# nf10_addon.net
KiCad netlist of a schematic drawn in Altium Designer
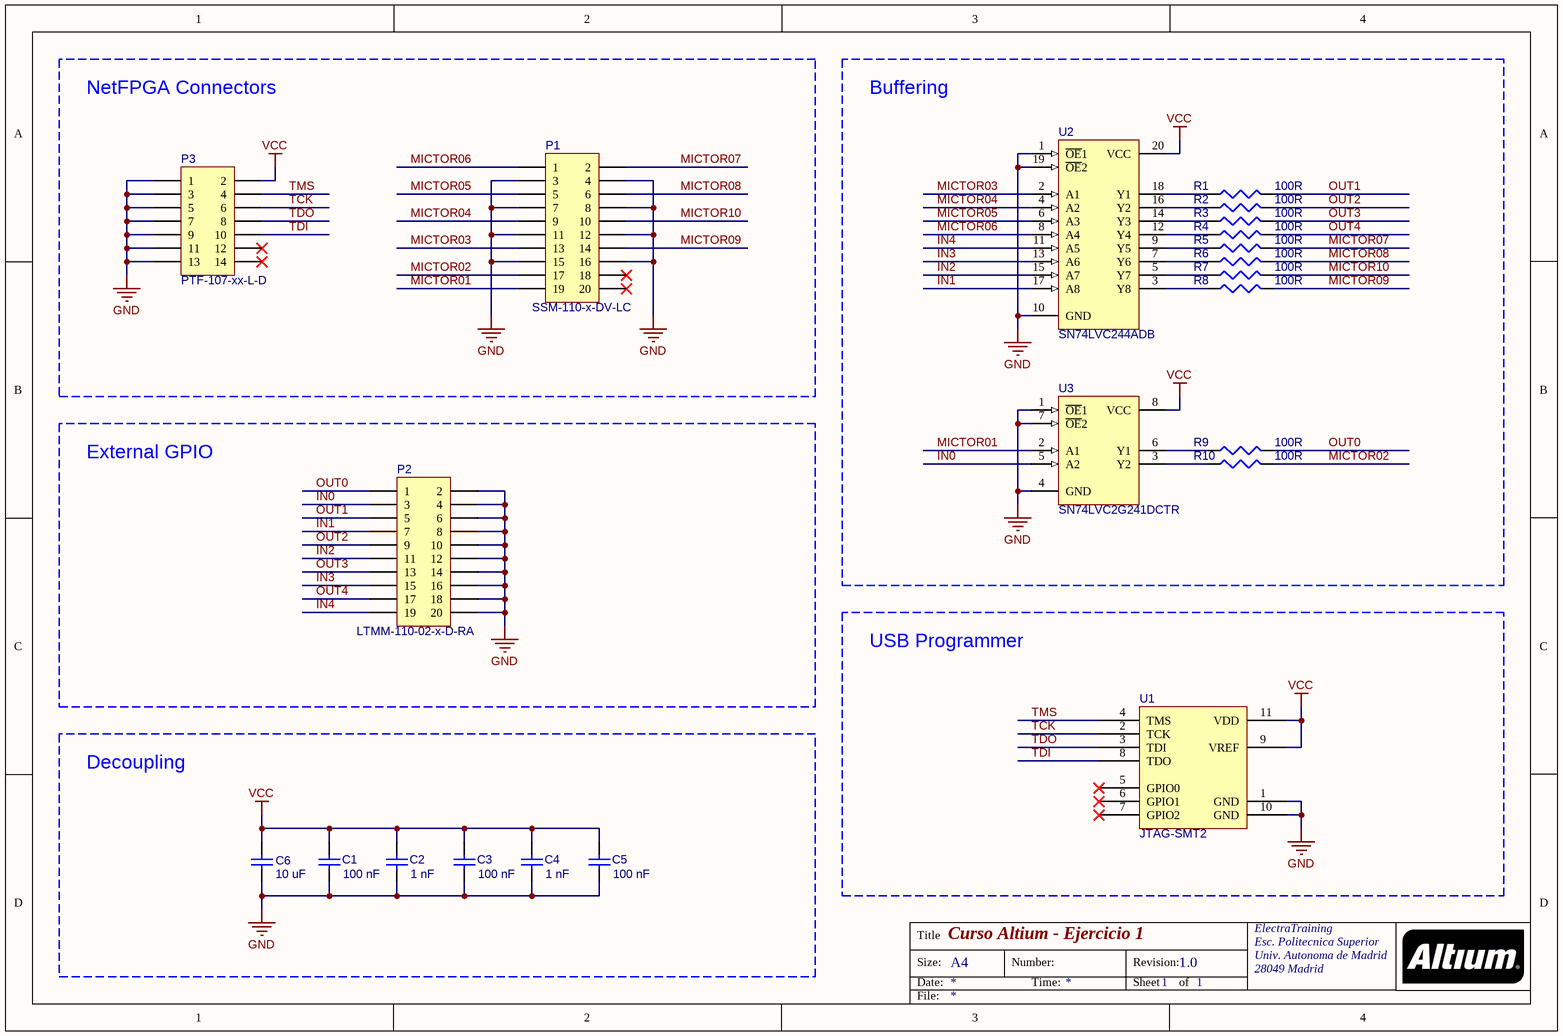
[diagram p0: nf10_addon.SchDoc]

(export (version "E")
  (design (tool "Eeschema 10.0.6"))
  (components
    (comp (ref "C1")
      (value "100 nF")
      (footprint "CAPC0603(1608)100_N")
      (description "Capacitor")
      (fields (field (name "Comment") "Cap") (field (name "PUBLISHER") "Altium Limited"))
      (libsource (lib "Miscellaneous Devices") (part "Cap"))
    )
    (comp (ref "C2")
      (value "1 nF")
      (footprint "CAPC0603(1608)100_N")
      (description "Capacitor")
      (fields (field (name "Comment") "Cap") (field (name "PUBLISHER") "Altium Limited"))
      (libsource (lib "Miscellaneous Devices") (part "Cap"))
    )
    (comp (ref "C3")
      (value "100 nF")
      (footprint "CAPC0603(1608)100_N")
      (description "Capacitor")
      (fields (field (name "Comment") "Cap") (field (name "PUBLISHER") "Altium Limited"))
      (libsource (lib "Miscellaneous Devices") (part "Cap"))
    )
    (comp (ref "C4")
      (value "1 nF")
      (footprint "CAPC0603(1608)100_N")
      (description "Capacitor")
      (fields (field (name "Comment") "Cap") (field (name "PUBLISHER") "Altium Limited"))
      (libsource (lib "Miscellaneous Devices") (part "Cap"))
    )
    (comp (ref "C5")
      (value "100 nF")
      (footprint "CAPC0603(1608)100_N")
      (description "Capacitor")
      (fields (field (name "Comment") "Cap") (field (name "PUBLISHER") "Altium Limited"))
      (libsource (lib "Miscellaneous Devices") (part "Cap"))
    )
    (comp (ref "C6")
      (value "10 uF")
      (footprint "CAPC1206(3216)100_N")
      (description "Capacitor")
      (fields (field (name "Comment") "Cap") (field (name "PUBLISHER") "Altium Limited"))
      (libsource (lib "Miscellaneous Devices") (part "Cap"))
    )
    (comp (ref "P1")
      (value "SSM-110-x-DV-LC")
      (footprint "SSM-110-X-DV-LC")
      (description "Samtec SSM-110-x-DV-LC")
      (fields (field (name "PUBLISHER") "Altium Limited"))
      (libsource (lib "nf10_addon") (part "SSM-110-x-DV-LC"))
    )
    (comp (ref "P2")
      (value "LTMM-110-02-x-D-RA")
      (footprint "LTMM-110-02-X-D-RA")
      (description "Samtec LTMM-110-02-x-D-RA")
      (fields (field (name "PUBLISHER") "Altium Limited"))
      (libsource (lib "nf10_addon") (part "LTMM-110-02-x-D-RA"))
    )
    (comp (ref "P3")
      (value "PTF-107-xx-L-D")
      (footprint "PTF-107-XX-L-D")
      (description "Samtec PTF-107-xx-L-D")
      (fields (field (name "PUBLISHER") "Altium Limited"))
      (libsource (lib "nf10_addon") (part "PTF-107-xx-L-D"))
    )
    (comp (ref "R1")
      (value "100R")
      (footprint "RESC0603(1608)_N")
      (description "Resistor")
      (fields (field (name "Comment") "Res3") (field (name "PUBLISHER") "Altium Limited"))
      (libsource (lib "Miscellaneous Devices") (part "Res3"))
    )
    (comp (ref "R2")
      (value "100R")
      (footprint "RESC0603(1608)_N")
      (description "Resistor")
      (fields (field (name "Comment") "Res3") (field (name "PUBLISHER") "Altium Limited"))
      (libsource (lib "Miscellaneous Devices") (part "Res3"))
    )
    (comp (ref "R3")
      (value "100R")
      (footprint "RESC0603(1608)_N")
      (description "Resistor")
      (fields (field (name "Comment") "Res3") (field (name "PUBLISHER") "Altium Limited"))
      (libsource (lib "Miscellaneous Devices") (part "Res3"))
    )
    (comp (ref "R4")
      (value "100R")
      (footprint "RESC0603(1608)_N")
      (description "Resistor")
      (fields (field (name "Comment") "Res3") (field (name "PUBLISHER") "Altium Limited"))
      (libsource (lib "Miscellaneous Devices") (part "Res3"))
    )
    (comp (ref "R5")
      (value "100R")
      (footprint "RESC0603(1608)_N")
      (description "Resistor")
      (fields (field (name "Comment") "Res3") (field (name "PUBLISHER") "Altium Limited"))
      (libsource (lib "Miscellaneous Devices") (part "Res3"))
    )
    (comp (ref "R6")
      (value "100R")
      (footprint "RESC0603(1608)_N")
      (description "Resistor")
      (fields (field (name "Comment") "Res3") (field (name "PUBLISHER") "Altium Limited"))
      (libsource (lib "Miscellaneous Devices") (part "Res3"))
    )
    (comp (ref "R7")
      (value "100R")
      (footprint "RESC0603(1608)_N")
      (description "Resistor")
      (fields (field (name "Comment") "Res3") (field (name "PUBLISHER") "Altium Limited"))
      (libsource (lib "Miscellaneous Devices") (part "Res3"))
    )
    (comp (ref "R8")
      (value "100R")
      (footprint "RESC0603(1608)_N")
      (description "Resistor")
      (fields (field (name "Comment") "Res3") (field (name "PUBLISHER") "Altium Limited"))
      (libsource (lib "Miscellaneous Devices") (part "Res3"))
    )
    (comp (ref "R9")
      (value "100R")
      (footprint "RESC0603(1608)_N")
      (description "Resistor")
      (fields (field (name "Comment") "Res3") (field (name "PUBLISHER") "Altium Limited"))
      (libsource (lib "Miscellaneous Devices") (part "Res3"))
    )
    (comp (ref "R10")
      (value "100R")
      (footprint "RESC0603(1608)_N")
      (description "Resistor")
      (fields (field (name "Comment") "Res3") (field (name "PUBLISHER") "Altium Limited"))
      (libsource (lib "Miscellaneous Devices") (part "Res3"))
    )
    (comp (ref "U1")
      (value "JTAG-SMT2")
      (footprint "JTAG-SMT2")
      (libsource (lib "NetFPGA10G_Addon") (part "JTAG_SMT2"))
    )
    (comp (ref "U2")
      (value "SN74LVC244ADB")
      (footprint "DB020_N")
      (description "Octal Buffer/Driver with 3-State Outputs")
      (fields (field (name "PUBLISHER") "Altium Limited"))
      (libsource (lib "TI Logic Buffer Line Driver") (part "SN74LVC244ADB"))
    )
    (comp (ref "U3")
      (value "SN74LVC2G241DCTR")
      (footprint "DCT08_N")
      (description "Quadruple Bus Buffer Gate with 3- State Outputs")
      (fields (field (name "PUBLISHER") "Altium Limited"))
      (libsource (lib "nf10_addon") (part "SN74LVC2G241DCTR"))
    )
  )
  (nets
    (net (code "1") (name "/IN0") (class "Default")
      (node (ref "P2") (pin "3") (pinfunction "3_3") (pintype "passive"))
      (node (ref "U3") (pin "5") (pinfunction "A2_5") (pintype "input"))
    )
    (net (code "2") (name "/IN1") (class "Default")
      (node (ref "P2") (pin "7") (pinfunction "7_7") (pintype "passive"))
      (node (ref "U2") (pin "17") (pinfunction "A8_17") (pintype "input"))
    )
    (net (code "3") (name "/IN2") (class "Default")
      (node (ref "P2") (pin "11") (pinfunction "11_11") (pintype "passive"))
      (node (ref "U2") (pin "15") (pinfunction "A7_15") (pintype "input"))
    )
    (net (code "4") (name "/IN3") (class "Default")
      (node (ref "P2") (pin "15") (pinfunction "15_15") (pintype "passive"))
      (node (ref "U2") (pin "13") (pinfunction "A6_13") (pintype "input"))
    )
    (net (code "5") (name "/IN4") (class "Default")
      (node (ref "P2") (pin "19") (pinfunction "19_19") (pintype "passive"))
      (node (ref "U2") (pin "11") (pinfunction "A5_11") (pintype "input"))
    )
    (net (code "6") (name "/MICTOR01") (class "Default")
      (node (ref "P1") (pin "19") (pinfunction "19_19") (pintype "passive"))
      (node (ref "U3") (pin "2") (pinfunction "A1_2") (pintype "input"))
    )
    (net (code "7") (name "/MICTOR02") (class "Default")
      (node (ref "P1") (pin "17") (pinfunction "17_17") (pintype "passive"))
      (node (ref "R10") (pin "2") (pinfunction "2_2") (pintype "passive"))
    )
    (net (code "8") (name "/MICTOR03") (class "Default")
      (node (ref "P1") (pin "13") (pinfunction "13_13") (pintype "passive"))
      (node (ref "U2") (pin "2") (pinfunction "A1_2") (pintype "input"))
    )
    (net (code "9") (name "/MICTOR04") (class "Default")
      (node (ref "P1") (pin "9") (pinfunction "9_9") (pintype "passive"))
      (node (ref "U2") (pin "4") (pinfunction "A2_4") (pintype "input"))
    )
    (net (code "10") (name "/MICTOR05") (class "Default")
      (node (ref "P1") (pin "5") (pinfunction "5_5") (pintype "passive"))
      (node (ref "U2") (pin "6") (pinfunction "A3_6") (pintype "input"))
    )
    (net (code "11") (name "/MICTOR06") (class "Default")
      (node (ref "P1") (pin "1") (pinfunction "1_1") (pintype "passive"))
      (node (ref "U2") (pin "8") (pinfunction "A4_8") (pintype "input"))
    )
    (net (code "12") (name "/MICTOR07") (class "Default")
      (node (ref "P1") (pin "2") (pinfunction "2_2") (pintype "passive"))
      (node (ref "R5") (pin "2") (pinfunction "2_2") (pintype "passive"))
    )
    (net (code "13") (name "/MICTOR08") (class "Default")
      (node (ref "P1") (pin "6") (pinfunction "6_6") (pintype "passive"))
      (node (ref "R6") (pin "2") (pinfunction "2_2") (pintype "passive"))
    )
    (net (code "14") (name "/MICTOR09") (class "Default")
      (node (ref "P1") (pin "14") (pinfunction "14_14") (pintype "passive"))
      (node (ref "R8") (pin "2") (pinfunction "2_2") (pintype "passive"))
    )
    (net (code "15") (name "/MICTOR10") (class "Default")
      (node (ref "P1") (pin "10") (pinfunction "10_10") (pintype "passive"))
      (node (ref "R7") (pin "2") (pinfunction "2_2") (pintype "passive"))
    )
    (net (code "16") (name "/OUT0") (class "Default")
      (node (ref "P2") (pin "1") (pinfunction "1_1") (pintype "passive"))
      (node (ref "R9") (pin "2") (pinfunction "2_2") (pintype "passive"))
    )
    (net (code "17") (name "/OUT1") (class "Default")
      (node (ref "P2") (pin "5") (pinfunction "5_5") (pintype "passive"))
      (node (ref "R1") (pin "2") (pinfunction "2_2") (pintype "passive"))
    )
    (net (code "18") (name "/OUT2") (class "Default")
      (node (ref "P2") (pin "9") (pinfunction "9_9") (pintype "passive"))
      (node (ref "R2") (pin "2") (pinfunction "2_2") (pintype "passive"))
    )
    (net (code "19") (name "/OUT3") (class "Default")
      (node (ref "P2") (pin "13") (pinfunction "13_13") (pintype "passive"))
      (node (ref "R3") (pin "2") (pinfunction "2_2") (pintype "passive"))
    )
    (net (code "20") (name "/OUT4") (class "Default")
      (node (ref "P2") (pin "17") (pinfunction "17_17") (pintype "passive"))
      (node (ref "R4") (pin "2") (pinfunction "2_2") (pintype "passive"))
    )
    (net (code "21") (name "/TCK") (class "Default")
      (node (ref "P3") (pin "6") (pinfunction "6_6") (pintype "passive"))
      (node (ref "U1") (pin "2") (pinfunction "TCK_2") (pintype "passive"))
    )
    (net (code "22") (name "/TDI") (class "Default")
      (node (ref "P3") (pin "10") (pinfunction "10_10") (pintype "passive"))
      (node (ref "U1") (pin "8") (pinfunction "TDO_8") (pintype "passive"))
    )
    (net (code "23") (name "/TDO") (class "Default")
      (node (ref "P3") (pin "8") (pinfunction "8_8") (pintype "passive"))
      (node (ref "U1") (pin "3") (pinfunction "TDI_3") (pintype "passive"))
    )
    (net (code "24") (name "/TMS") (class "Default")
      (node (ref "P3") (pin "4") (pinfunction "4_4") (pintype "passive"))
      (node (ref "U1") (pin "4") (pinfunction "TMS_4") (pintype "passive"))
    )
    (net (code "25") (name "GND") (class "Default")
      (node (ref "C1") (pin "1") (pinfunction "1_1") (pintype "passive"))
      (node (ref "C2") (pin "1") (pinfunction "1_1") (pintype "passive"))
      (node (ref "C3") (pin "1") (pinfunction "1_1") (pintype "passive"))
      (node (ref "C4") (pin "1") (pinfunction "1_1") (pintype "passive"))
      (node (ref "C5") (pin "1") (pinfunction "1_1") (pintype "passive"))
      (node (ref "C6") (pin "1") (pinfunction "1_1") (pintype "passive"))
      (node (ref "P1") (pin "11") (pinfunction "11_11") (pintype "passive"))
      (node (ref "P1") (pin "12") (pinfunction "12_12") (pintype "passive"))
      (node (ref "P1") (pin "15") (pinfunction "15_15") (pintype "passive"))
      (node (ref "P1") (pin "16") (pinfunction "16_16") (pintype "passive"))
      (node (ref "P1") (pin "3") (pinfunction "3_3") (pintype "passive"))
      (node (ref "P1") (pin "4") (pinfunction "4_4") (pintype "passive"))
      (node (ref "P1") (pin "7") (pinfunction "7_7") (pintype "passive"))
      (node (ref "P1") (pin "8") (pinfunction "8_8") (pintype "passive"))
      (node (ref "P2") (pin "10") (pinfunction "10_10") (pintype "passive"))
      (node (ref "P2") (pin "12") (pinfunction "12_12") (pintype "passive"))
      (node (ref "P2") (pin "14") (pinfunction "14_14") (pintype "passive"))
      (node (ref "P2") (pin "16") (pinfunction "16_16") (pintype "passive"))
      (node (ref "P2") (pin "18") (pinfunction "18_18") (pintype "passive"))
      (node (ref "P2") (pin "2") (pinfunction "2_2") (pintype "passive"))
      (node (ref "P2") (pin "20") (pinfunction "20_20") (pintype "passive"))
      (node (ref "P2") (pin "4") (pinfunction "4_4") (pintype "passive"))
      (node (ref "P2") (pin "6") (pinfunction "6_6") (pintype "passive"))
      (node (ref "P2") (pin "8") (pinfunction "8_8") (pintype "passive"))
      (node (ref "P3") (pin "1") (pinfunction "1_1") (pintype "passive"))
      (node (ref "P3") (pin "11") (pinfunction "11_11") (pintype "passive"))
      (node (ref "P3") (pin "13") (pinfunction "13_13") (pintype "passive"))
      (node (ref "P3") (pin "3") (pinfunction "3_3") (pintype "passive"))
      (node (ref "P3") (pin "5") (pinfunction "5_5") (pintype "passive"))
      (node (ref "P3") (pin "7") (pinfunction "7_7") (pintype "passive"))
      (node (ref "P3") (pin "9") (pinfunction "9_9") (pintype "passive"))
      (node (ref "U1") (pin "1") (pinfunction "GND_1") (pintype "passive"))
      (node (ref "U1") (pin "10") (pinfunction "GND_10") (pintype "passive"))
      (node (ref "U2") (pin "1") (pinfunction "~{OE}1_1") (pintype "input"))
      (node (ref "U2") (pin "10") (pinfunction "GND_10") (pintype "power_in"))
      (node (ref "U2") (pin "19") (pinfunction "~{OE}2_19") (pintype "input"))
      (node (ref "U3") (pin "1") (pinfunction "~{OE}1_1") (pintype "input"))
      (node (ref "U3") (pin "4") (pinfunction "GND_4") (pintype "power_in"))
      (node (ref "U3") (pin "7") (pinfunction "~{OE}2_7") (pintype "input"))
    )
    (net (code "26") (name "Net-(U2-Y1)") (class "Default")
      (node (ref "R1") (pin "1") (pinfunction "1_1") (pintype "passive"))
      (node (ref "U2") (pin "18") (pinfunction "Y1_18") (pintype "tri_state"))
    )
    (net (code "27") (name "Net-(U2-Y2)") (class "Default")
      (node (ref "R2") (pin "1") (pinfunction "1_1") (pintype "passive"))
      (node (ref "U2") (pin "16") (pinfunction "Y2_16") (pintype "tri_state"))
    )
    (net (code "28") (name "Net-(U2-Y3)") (class "Default")
      (node (ref "R3") (pin "1") (pinfunction "1_1") (pintype "passive"))
      (node (ref "U2") (pin "14") (pinfunction "Y3_14") (pintype "tri_state"))
    )
    (net (code "29") (name "Net-(U2-Y4)") (class "Default")
      (node (ref "R4") (pin "1") (pinfunction "1_1") (pintype "passive"))
      (node (ref "U2") (pin "12") (pinfunction "Y4_12") (pintype "tri_state"))
    )
    (net (code "30") (name "Net-(U2-Y5)") (class "Default")
      (node (ref "R5") (pin "1") (pinfunction "1_1") (pintype "passive"))
      (node (ref "U2") (pin "9") (pinfunction "Y5_9") (pintype "tri_state"))
    )
    (net (code "31") (name "Net-(U2-Y6)") (class "Default")
      (node (ref "R6") (pin "1") (pinfunction "1_1") (pintype "passive"))
      (node (ref "U2") (pin "7") (pinfunction "Y6_7") (pintype "tri_state"))
    )
    (net (code "32") (name "Net-(U2-Y7)") (class "Default")
      (node (ref "R7") (pin "1") (pinfunction "1_1") (pintype "passive"))
      (node (ref "U2") (pin "5") (pinfunction "Y7_5") (pintype "tri_state"))
    )
    (net (code "33") (name "Net-(U2-Y8)") (class "Default")
      (node (ref "R8") (pin "1") (pinfunction "1_1") (pintype "passive"))
      (node (ref "U2") (pin "3") (pinfunction "Y8_3") (pintype "tri_state"))
    )
    (net (code "34") (name "Net-(U3-Y1)") (class "Default")
      (node (ref "R9") (pin "1") (pinfunction "1_1") (pintype "passive"))
      (node (ref "U3") (pin "6") (pinfunction "Y1_6") (pintype "tri_state"))
    )
    (net (code "35") (name "Net-(U3-Y2)") (class "Default")
      (node (ref "R10") (pin "1") (pinfunction "1_1") (pintype "passive"))
      (node (ref "U3") (pin "3") (pinfunction "Y2_3") (pintype "tri_state"))
    )
    (net (code "36") (name "VCC") (class "Default")
      (node (ref "C1") (pin "2") (pinfunction "2_2") (pintype "passive"))
      (node (ref "C2") (pin "2") (pinfunction "2_2") (pintype "passive"))
      (node (ref "C3") (pin "2") (pinfunction "2_2") (pintype "passive"))
      (node (ref "C4") (pin "2") (pinfunction "2_2") (pintype "passive"))
      (node (ref "C5") (pin "2") (pinfunction "2_2") (pintype "passive"))
      (node (ref "C6") (pin "2") (pinfunction "2_2") (pintype "passive"))
      (node (ref "P3") (pin "2") (pinfunction "2_2") (pintype "passive"))
      (node (ref "U1") (pin "11") (pinfunction "VDD_11") (pintype "passive"))
      (node (ref "U1") (pin "9") (pinfunction "VREF_9") (pintype "passive"))
      (node (ref "U2") (pin "20") (pinfunction "VCC_20") (pintype "power_in"))
      (node (ref "U3") (pin "8") (pinfunction "VCC_8") (pintype "power_in"))
    )
    (net (code "37") (name "unconnected-(P1-Pad18)") (class "Default")
      (node (ref "P1") (pin "18") (pinfunction "18_18") (pintype "passive+no_connect"))
    )
    (net (code "38") (name "unconnected-(P1-Pad20)") (class "Default")
      (node (ref "P1") (pin "20") (pinfunction "20_20") (pintype "passive+no_connect"))
    )
    (net (code "39") (name "unconnected-(P3-Pad12)") (class "Default")
      (node (ref "P3") (pin "12") (pinfunction "12_12") (pintype "passive+no_connect"))
    )
    (net (code "40") (name "unconnected-(P3-Pad14)") (class "Default")
      (node (ref "P3") (pin "14") (pinfunction "14_14") (pintype "passive+no_connect"))
    )
    (net (code "41") (name "unconnected-(U1-GPIO0-Pad5)") (class "Default")
      (node (ref "U1") (pin "5") (pinfunction "GPIO0_5") (pintype "passive+no_connect"))
    )
    (net (code "42") (name "unconnected-(U1-GPIO1-Pad6)") (class "Default")
      (node (ref "U1") (pin "6") (pinfunction "GPIO1_6") (pintype "passive+no_connect"))
    )
    (net (code "43") (name "unconnected-(U1-GPIO2-Pad7)") (class "Default")
      (node (ref "U1") (pin "7") (pinfunction "GPIO2_7") (pintype "passive+no_connect"))
    )
  )
)
